# HMC5883_module.net
KiCad netlist of a schematic drawn in Altium Designer
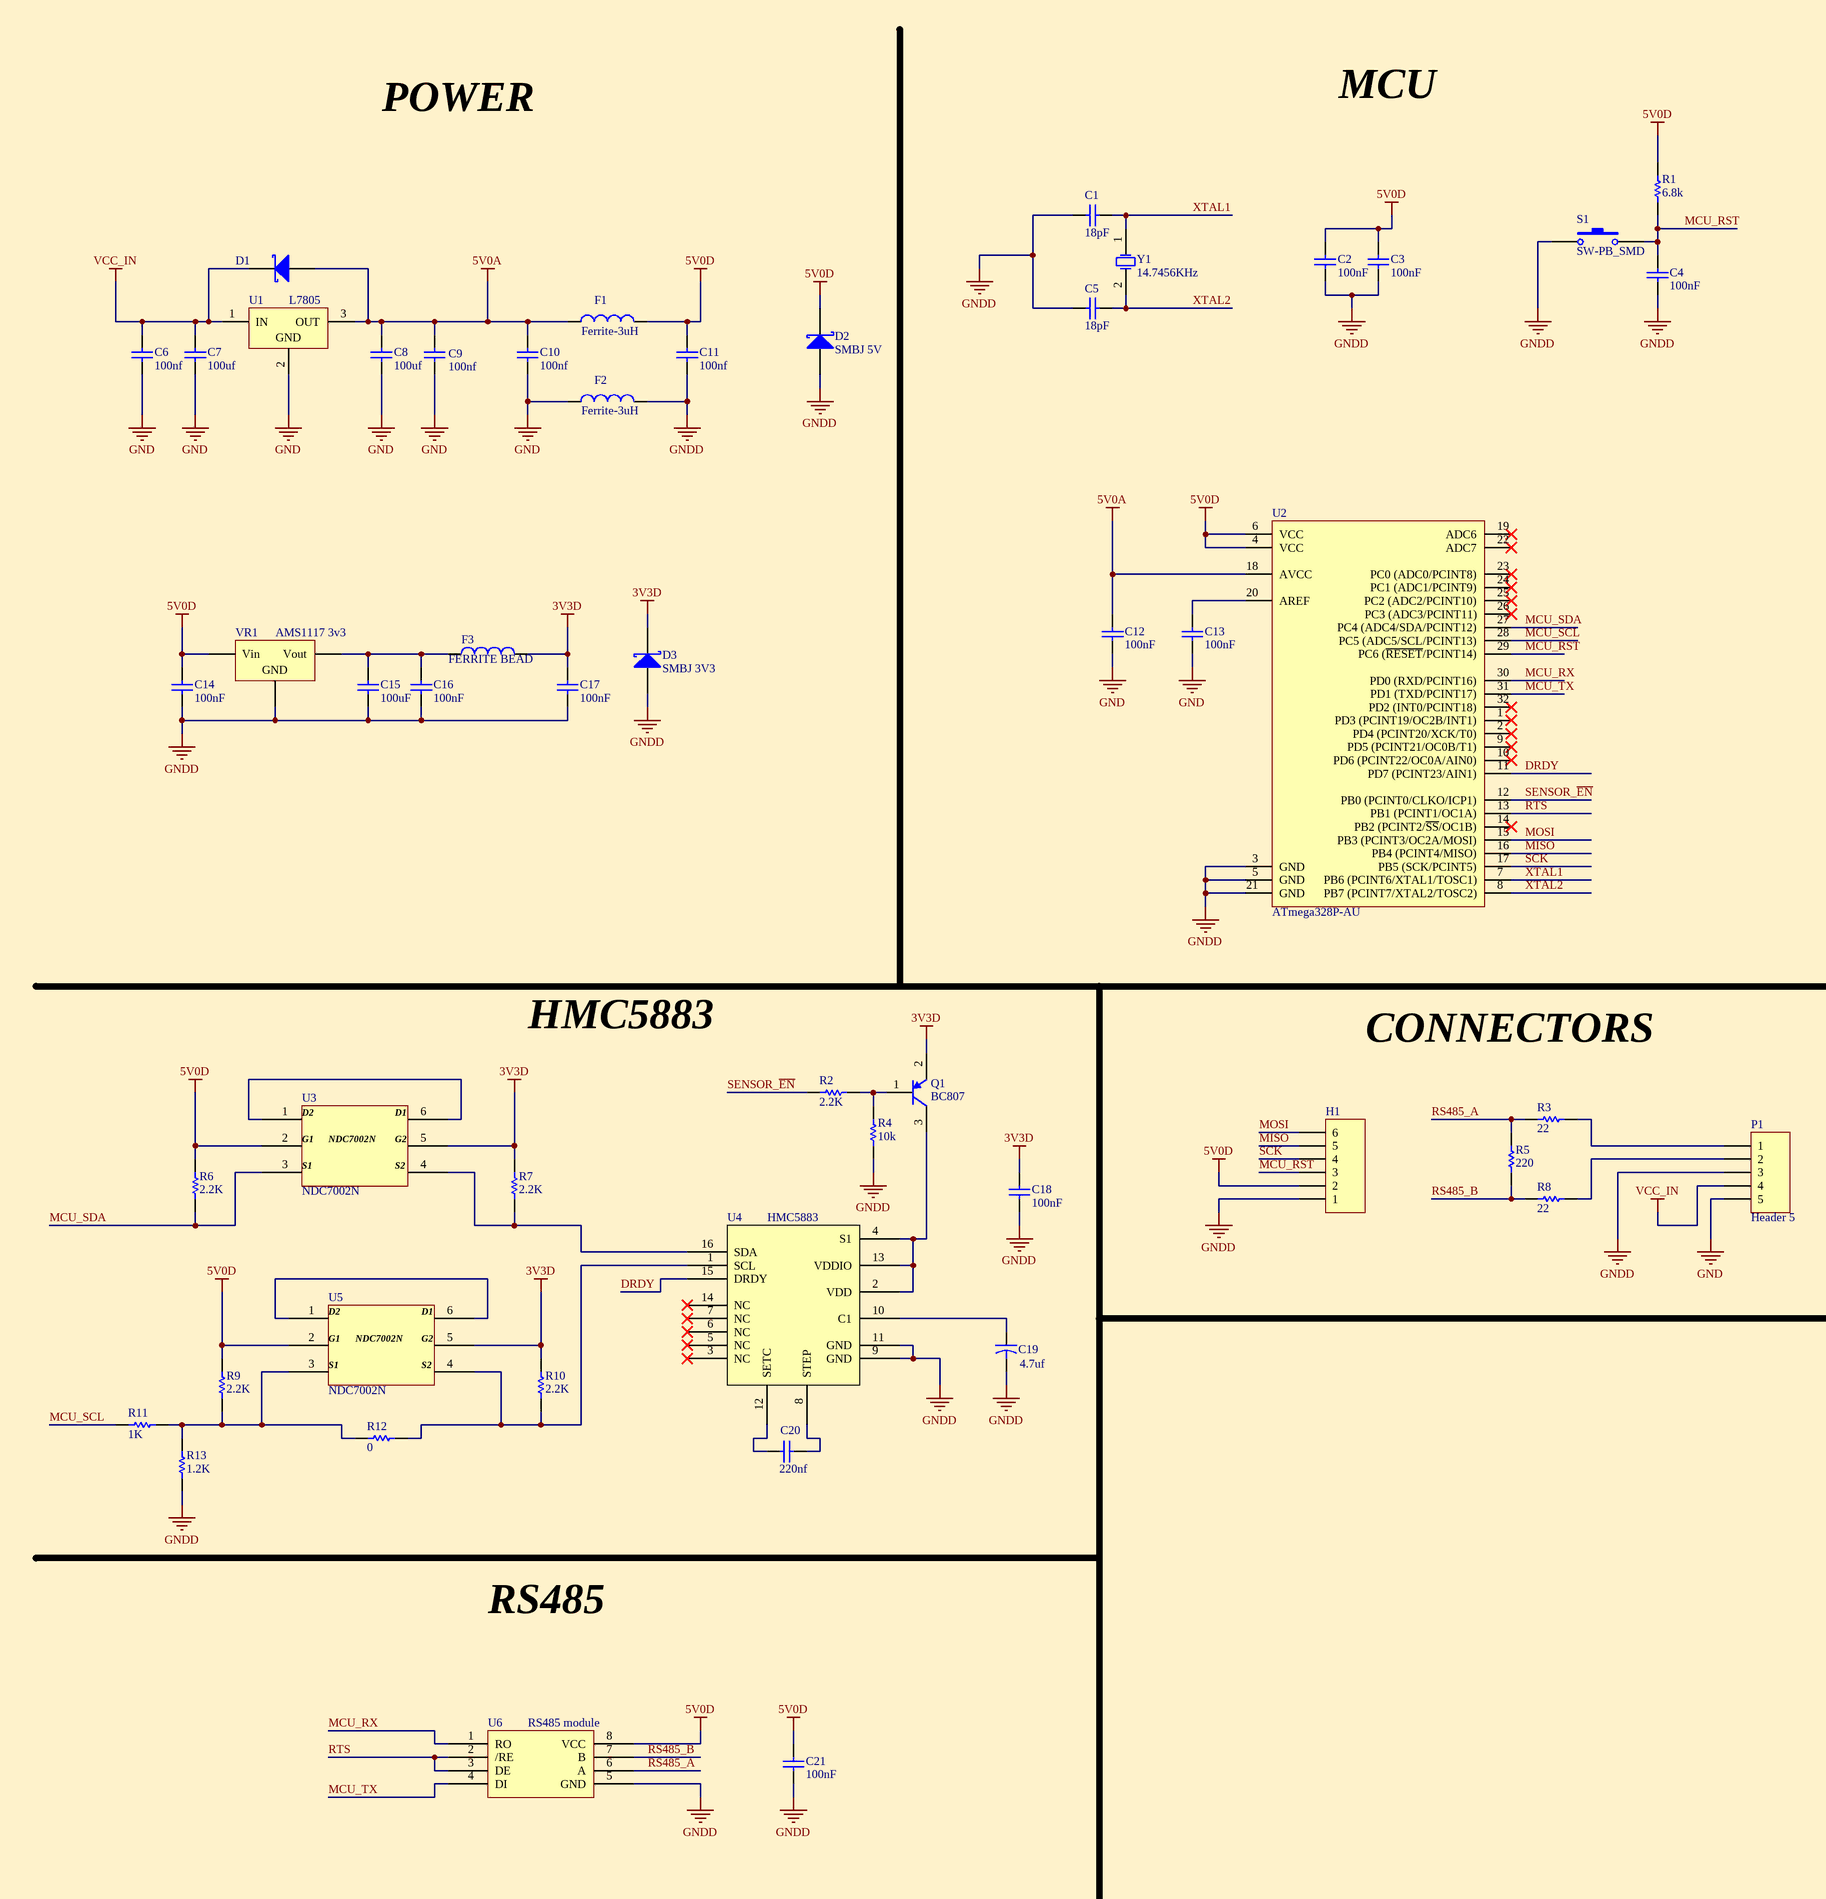
[diagram p0: HMC5883_module.SchDoc, left]
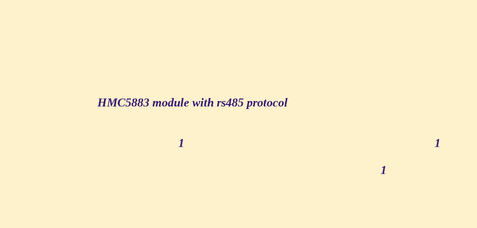
[diagram p1: HMC5883_module.SchDoc, right]

(export (version "E")
  (design (tool "Eeschema 10.0.6"))
  (components
    (comp (ref "C1")
      (value "18pF")
      (footprint "1206")
      (description "Capacitor")
      (fields (field (name "PUBLISHER") "Altium Limited"))
      (libsource (lib "Miscellaneous Devices") (part "Cap"))
    )
    (comp (ref "C2")
      (value "100nF")
      (footprint "1206")
      (description "Capacitor")
      (fields (field (name "PUBLISHER") "Altium Limited"))
      (libsource (lib "Miscellaneous Devices") (part "Cap"))
    )
    (comp (ref "C3")
      (value "100nF")
      (footprint "1206")
      (description "Capacitor")
      (fields (field (name "PUBLISHER") "Altium Limited"))
      (libsource (lib "Miscellaneous Devices") (part "Cap"))
    )
    (comp (ref "C4")
      (value "100nF")
      (footprint "1206")
      (description "Capacitor")
      (fields (field (name "PUBLISHER") "Altium Limited"))
      (libsource (lib "Miscellaneous Devices") (part "Cap"))
    )
    (comp (ref "C5")
      (value "18pF")
      (footprint "1206")
      (description "Capacitor")
      (fields (field (name "PUBLISHER") "Altium Limited"))
      (libsource (lib "Miscellaneous Devices") (part "Cap"))
    )
    (comp (ref "C6")
      (value "100nf")
      (footprint "1206")
      (description "Capacitor, 1206")
      (fields (field (name "PUBLISHER") "Altium Limited"))
      (libsource (lib "Miscellaneous Devices") (part "Cap"))
    )
    (comp (ref "C7")
      (value "100uf")
      (footprint "1206")
      (description "Capacitor, 1206")
      (fields (field (name "PUBLISHER") "Altium Limited"))
      (libsource (lib "Miscellaneous Devices") (part "Cap"))
    )
    (comp (ref "C8")
      (value "100uf")
      (footprint "1206")
      (description "Capacitor, 1206")
      (fields (field (name "PUBLISHER") "Altium Limited"))
      (libsource (lib "Miscellaneous Devices") (part "Cap"))
    )
    (comp (ref "C9")
      (value "100nf")
      (footprint "1206")
      (description "Capacitor, 1206")
      (fields (field (name "PUBLISHER") "Altium Limited"))
      (libsource (lib "Miscellaneous Devices") (part "Cap"))
    )
    (comp (ref "C10")
      (value "100nf")
      (footprint "1206")
      (description "Capacitor, 1206")
      (fields (field (name "PUBLISHER") "Altium Limited"))
      (libsource (lib "Miscellaneous Devices") (part "Cap"))
    )
    (comp (ref "C11")
      (value "100nf")
      (footprint "1206")
      (description "Capacitor, 1206")
      (fields (field (name "PUBLISHER") "Altium Limited"))
      (libsource (lib "Miscellaneous Devices") (part "Cap"))
    )
    (comp (ref "C12")
      (value "100nF")
      (footprint "1206")
      (description "Capacitor")
      (fields (field (name "PUBLISHER") "Altium Limited"))
      (libsource (lib "Miscellaneous Devices") (part "Cap"))
    )
    (comp (ref "C13")
      (value "100nF")
      (footprint "1206")
      (description "Capacitor")
      (fields (field (name "PUBLISHER") "Altium Limited"))
      (libsource (lib "Miscellaneous Devices") (part "Cap"))
    )
    (comp (ref "C14")
      (value "100nF")
      (footprint "1206")
      (description "Capacitor")
      (fields (field (name "Comment") "Cap") (field (name "PUBLISHER") "Altium Limited"))
      (libsource (lib "Miscellaneous Devices") (part "Cap"))
    )
    (comp (ref "C15")
      (value "100uF")
      (footprint "1206")
      (description "Capacitor")
      (fields (field (name "Comment") "Cap") (field (name "PUBLISHER") "Altium Limited"))
      (libsource (lib "Miscellaneous Devices") (part "Cap"))
    )
    (comp (ref "C16")
      (value "100nF")
      (footprint "1206")
      (description "Capacitor")
      (fields (field (name "Comment") "Cap") (field (name "PUBLISHER") "Altium Limited"))
      (libsource (lib "Miscellaneous Devices") (part "Cap"))
    )
    (comp (ref "C17")
      (value "100nF")
      (footprint "1206")
      (description "Capacitor")
      (fields (field (name "Comment") "Cap") (field (name "PUBLISHER") "Altium Limited"))
      (libsource (lib "Miscellaneous Devices") (part "Cap"))
    )
    (comp (ref "C18")
      (value "100nF")
      (footprint "1206")
      (description "Capacitor")
      (fields (field (name "Comment") "Cap") (field (name "PUBLISHER") "Altium Limited"))
      (libsource (lib "Miscellaneous Devices") (part "Cap"))
    )
    (comp (ref "C19")
      (value "4.7uf")
      (footprint "CAP_SMD_A")
      (description "TAN")
      (fields (field (name "Comment") "Cap2") (field (name "PUBLISHER") "Altium Limited"))
      (libsource (lib "Miscellaneous Devices") (part "Cap2"))
    )
    (comp (ref "C20")
      (value "220nf")
      (footprint "1206")
      (description "Capacitor")
      (fields (field (name "Comment") "Cap") (field (name "PUBLISHER") "Altium Limited"))
      (libsource (lib "Miscellaneous Devices") (part "Cap"))
    )
    (comp (ref "C21")
      (value "100nF")
      (footprint "1206")
      (description "Capacitor")
      (fields (field (name "Comment") "Cap") (field (name "PUBLISHER") "Altium Limited"))
      (libsource (lib "Miscellaneous Devices") (part "Cap"))
    )
    (comp (ref "D1")
      (value "D Schottky")
      (footprint "ZINER")
      (description "Schottky Diode, 1N4148")
      (fields (field (name "PUBLISHER") "Altium Limited"))
      (libsource (lib "Miscellaneous Devices") (part "D Schottky"))
    )
    (comp (ref "D2")
      (value "SMBJ 5V")
      (footprint "TVS")
      (description "Schottky Rectifier")
      (fields (field (name "PUBLISHER") "Altium Limited"))
      (libsource (lib "Miscellaneous Devices") (part "Diode 18TQ045"))
    )
    (comp (ref "D3")
      (value "SMBJ 3V3")
      (footprint "TVS")
      (description "TVS")
      (fields (field (name "PUBLISHER") "Altium Limited"))
      (libsource (lib "Miscellaneous Devices") (part "Diode 18TQ045"))
    )
    (comp (ref "F1")
      (value "Ferrite-3uH")
      (footprint "1206")
      (description "Inductor")
      (fields (field (name "PUBLISHER") "Altium Limited"))
      (libsource (lib "Miscellaneous Devices") (part "Inductor"))
    )
    (comp (ref "F2")
      (value "Ferrite-3uH")
      (footprint "1206")
      (description "Inductor")
      (fields (field (name "PUBLISHER") "Altium Limited"))
      (libsource (lib "Miscellaneous Devices") (part "Inductor"))
    )
    (comp (ref "F3")
      (value "FERRITE BEAD")
      (footprint "1206")
      (fields (field (name "PUBLISHER") "Altium Limited"))
      (libsource (lib "Miscellaneous Devices") (part "Inductor"))
    )
    (comp (ref "H1")
      (value "White SMD Connector 6pin")
      (footprint "White SMD Connector 6pin B")
      (fields (field (name "PUBLISHER") "Altium Limited"))
      (libsource (lib "Miscellaneous Connectors") (part "Header 6"))
    )
    (comp (ref "P1")
      (value "Header 5")
      (footprint "HDR1X5")
      (description "Header, 5-Pin")
      (fields (field (name "PUBLISHER") "Altium Limited"))
      (libsource (lib "Miscellaneous Connectors") (part "Header 5"))
    )
    (comp (ref "Q1")
      (value "BC807")
      (footprint "SOT-23")
      (description "PNP General Purpose Amplifier")
      (fields (field (name "PUBLISHER") "Altium Limited"))
      (libsource (lib "Miscellaneous Devices") (part "2N3906"))
    )
    (comp (ref "R1")
      (value "6.8k")
      (footprint "1206")
      (description "Resistor, 6.8k")
      (fields (field (name "PUBLISHER") "Altium Limited"))
      (libsource (lib "Miscellaneous Devices") (part "Res1"))
    )
    (comp (ref "R2")
      (value "2.2K")
      (footprint "1206")
      (description "Resistor")
      (fields (field (name "PUBLISHER") "Altium Limited"))
      (libsource (lib "Miscellaneous Devices") (part "Res1"))
    )
    (comp (ref "R3")
      (value "22")
      (footprint "1206")
      (description "Resistor")
      (fields (field (name "PUBLISHER") "Altium Limited"))
      (libsource (lib "Miscellaneous Devices") (part "Res1"))
    )
    (comp (ref "R4")
      (value "10k")
      (footprint "1206")
      (description "Resistor")
      (fields (field (name "PUBLISHER") "Altium Limited"))
      (libsource (lib "Miscellaneous Devices") (part "Res1"))
    )
    (comp (ref "R5")
      (value "220")
      (footprint "1206")
      (description "Resistor")
      (fields (field (name "PUBLISHER") "Altium Limited"))
      (libsource (lib "Miscellaneous Devices") (part "Res1"))
    )
    (comp (ref "R6")
      (value "2.2K")
      (footprint "1206")
      (description "Resistor")
      (fields (field (name "PUBLISHER") "Altium Limited"))
      (libsource (lib "Miscellaneous Devices") (part "Res1"))
    )
    (comp (ref "R7")
      (value "2.2K")
      (footprint "1206")
      (description "Resistor")
      (fields (field (name "PUBLISHER") "Altium Limited"))
      (libsource (lib "Miscellaneous Devices") (part "Res1"))
    )
    (comp (ref "R8")
      (value "22")
      (footprint "1206")
      (description "Resistor")
      (fields (field (name "PUBLISHER") "Altium Limited"))
      (libsource (lib "Miscellaneous Devices") (part "Res1"))
    )
    (comp (ref "R9")
      (value "2.2K")
      (footprint "1206")
      (description "Resistor")
      (fields (field (name "PUBLISHER") "Altium Limited"))
      (libsource (lib "Miscellaneous Devices") (part "Res1"))
    )
    (comp (ref "R10")
      (value "2.2K")
      (footprint "1206")
      (description "Resistor")
      (fields (field (name "PUBLISHER") "Altium Limited"))
      (libsource (lib "Miscellaneous Devices") (part "Res1"))
    )
    (comp (ref "R11")
      (value "1K")
      (footprint "1206")
      (description "Resistor")
      (fields (field (name "PUBLISHER") "Altium Limited"))
      (libsource (lib "Miscellaneous Devices") (part "Res1"))
    )
    (comp (ref "R12")
      (value "0")
      (footprint "1206")
      (description "Resistor")
      (fields (field (name "PUBLISHER") "Altium Limited"))
      (libsource (lib "Miscellaneous Devices") (part "Res1"))
    )
    (comp (ref "R13")
      (value "1.2K")
      (footprint "1206")
      (description "Resistor")
      (fields (field (name "PUBLISHER") "Altium Limited"))
      (libsource (lib "Miscellaneous Devices") (part "Res1"))
    )
    (comp (ref "S1")
      (value "SW-PB_SMD")
      (footprint "PB4x3.2")
      (description "Switch")
      (fields (field (name "PUBLISHER") "Altium Limited"))
      (libsource (lib "Miscellaneous Devices") (part "SW-PB"))
    )
    (comp (ref "U1")
      (value "L7805")
      (footprint "DPAK")
      (description "Positive Voltage Regulator")
      (fields (field (name "PUBLISHER") "Altium Limited"))
      (libsource (lib "ST Power Mgt Voltage Regulator") (part "L7805CD2T"))
    )
    (comp (ref "U2")
      (value "ATmega328P-AU")
      (footprint "32A_L")
      (fields (field (name "PUBLISHER") "Altium Limited"))
      (libsource (lib "Library") (part "ATmega328P-AU"))
    )
    (comp (ref "U3") (value "NDC7002N") (footprint "SOP6") (libsource (lib "NDC7002N") (part "NDC7002N")))
    (comp (ref "U4") (value "HMC5883") (footprint "LCC16") (libsource (lib "Library") (part "HMC5883")))
    (comp (ref "U5") (value "NDC7002N") (footprint "SOP6") (libsource (lib "NDC7002N") (part "NDC7002N")))
    (comp (ref "U6")
      (value "RS485 module")
      (footprint "SOP8")
      (libsource (lib "Schlib_RS485") (part "rs485"))
    )
    (comp (ref "VR1")
      (value "AMS1117 3v3")
      (footprint "LD1117")
      (description "Voltage Regulator")
      (fields (field (name "PUBLISHER") "Altium Limited"))
      (libsource (lib "Miscellaneous Devices") (part "Volt Reg"))
    )
    (comp (ref "Y1")
      (value "14.7456KHz")
      (footprint "XTAL_SMD")
      (description "Crystal Oscillator, 14.7456KHz")
      (fields (field (name "PUBLISHER") "Altium Limited"))
      (libsource (lib "Miscellaneous Devices") (part "XTAL"))
    )
  )
  (nets
    (net (code "1") (name "/DRDY") (class "Default")
      (node (ref "U2") (pin "11") (pinfunction "PD7_(PCINT23/AIN1)_11") (pintype "passive"))
      (node (ref "U4") (pin "15") (pinfunction "DRDY_15") (pintype "passive"))
    )
    (net (code "2") (name "/MCU_RST") (class "Default")
      (node (ref "C4") (pin "2") (pinfunction "2_2") (pintype "passive"))
      (node (ref "H1") (pin "3") (pinfunction "3_3") (pintype "passive"))
      (node (ref "R1") (pin "2") (pinfunction "2_2") (pintype "passive"))
      (node (ref "S1") (pin "2") (pinfunction "2_2") (pintype "passive"))
      (node (ref "U2") (pin "29") (pinfunction "PC6_(~{RESET}/PCINT14)_29") (pintype "passive"))
    )
    (net (code "3") (name "/MCU_RX") (class "Default")
      (node (ref "U2") (pin "30") (pinfunction "PD0_(RXD/PCINT16)_30") (pintype "passive"))
      (node (ref "U6") (pin "1") (pinfunction "RO_1") (pintype "passive"))
    )
    (net (code "4") (name "/MCU_SCL") (class "Default")
      (node (ref "R11") (pin "1") (pinfunction "1_1") (pintype "passive"))
      (node (ref "U2") (pin "28") (pinfunction "PC5_(ADC5/SCL/PCINT13)_28") (pintype "passive"))
    )
    (net (code "5") (name "/MCU_SDA") (class "Default")
      (node (ref "R6") (pin "1") (pinfunction "1_1") (pintype "passive"))
      (node (ref "U2") (pin "27") (pinfunction "PC4_(ADC4/SDA/PCINT12)_27") (pintype "passive"))
      (node (ref "U3") (pin "3") (pintype "passive"))
    )
    (net (code "6") (name "/MCU_TX") (class "Default")
      (node (ref "U2") (pin "31") (pinfunction "PD1_(TXD/PCINT17)_31") (pintype "passive"))
      (node (ref "U6") (pin "4") (pinfunction "DI_4") (pintype "passive"))
    )
    (net (code "7") (name "/MISO") (class "Default")
      (node (ref "H1") (pin "5") (pinfunction "5_5") (pintype "passive"))
      (node (ref "U2") (pin "16") (pinfunction "PB4_(PCINT4/MISO)_16") (pintype "passive"))
    )
    (net (code "8") (name "/MOSI") (class "Default")
      (node (ref "H1") (pin "6") (pinfunction "6_6") (pintype "passive"))
      (node (ref "U2") (pin "15") (pinfunction "PB3_(PCINT3/OC2A/MOSI)_15") (pintype "passive"))
    )
    (net (code "9") (name "/RS485_A") (class "Default")
      (node (ref "R3") (pin "1") (pinfunction "1_1") (pintype "passive"))
      (node (ref "R5") (pin "1") (pinfunction "1_1") (pintype "passive"))
      (node (ref "U6") (pin "6") (pinfunction "A_6") (pintype "passive"))
    )
    (net (code "10") (name "/RS485_B") (class "Default")
      (node (ref "R5") (pin "2") (pinfunction "2_2") (pintype "passive"))
      (node (ref "R8") (pin "1") (pinfunction "1_1") (pintype "passive"))
      (node (ref "U6") (pin "7") (pinfunction "B_7") (pintype "passive"))
    )
    (net (code "11") (name "/RTS") (class "Default")
      (node (ref "U2") (pin "13") (pinfunction "PB1_(PCINT1/OC1A)_13") (pintype "passive"))
      (node (ref "U6") (pin "2") (pinfunction "/RE_2") (pintype "passive"))
      (node (ref "U6") (pin "3") (pinfunction "DE_3") (pintype "passive"))
    )
    (net (code "12") (name "/SCK") (class "Default")
      (node (ref "H1") (pin "4") (pinfunction "4_4") (pintype "passive"))
      (node (ref "U2") (pin "17") (pinfunction "PB5_(SCK/PCINT5)_17") (pintype "passive"))
    )
    (net (code "13") (name "/SENSOR_~{EN}") (class "Default")
      (node (ref "R2") (pin "2") (pinfunction "2_2") (pintype "passive"))
      (node (ref "U2") (pin "12") (pinfunction "PB0_(PCINT0/CLKO/ICP1)_12") (pintype "passive"))
    )
    (net (code "14") (name "/XTAL1") (class "Default")
      (node (ref "C1") (pin "2") (pinfunction "2_2") (pintype "passive"))
      (node (ref "U2") (pin "7") (pinfunction "PB6_(PCINT6/XTAL1/TOSC1)_7") (pintype "passive"))
      (node (ref "Y1") (pin "1") (pinfunction "OSC1_1") (pintype "passive"))
    )
    (net (code "15") (name "/XTAL2") (class "Default")
      (node (ref "C5") (pin "2") (pinfunction "2_2") (pintype "passive"))
      (node (ref "U2") (pin "8") (pinfunction "PB7_(PCINT7/XTAL2/TOSC2)_8") (pintype "passive"))
      (node (ref "Y1") (pin "2") (pinfunction "OSC2_2") (pintype "passive"))
    )
    (net (code "16") (name "3V3D") (class "Default")
      (node (ref "C17") (pin "2") (pinfunction "2_2") (pintype "passive"))
      (node (ref "C18") (pin "2") (pinfunction "2_2") (pintype "passive"))
      (node (ref "D3") (pin "1") (pinfunction "K_1") (pintype "passive"))
      (node (ref "F3") (pin "2") (pinfunction "2_2") (pintype "passive"))
      (node (ref "Q1") (pin "2") (pinfunction "E_2") (pintype "passive"))
      (node (ref "R10") (pin "2") (pinfunction "2_2") (pintype "passive"))
      (node (ref "R7") (pin "2") (pinfunction "2_2") (pintype "passive"))
      (node (ref "U3") (pin "5") (pinfunction "5_5") (pintype "passive"))
      (node (ref "U5") (pin "5") (pinfunction "5_5") (pintype "passive"))
    )
    (net (code "17") (name "5V0A") (class "Default")
      (node (ref "C10") (pin "2") (pinfunction "2_2") (pintype "passive"))
      (node (ref "C12") (pin "2") (pinfunction "2_2") (pintype "passive"))
      (node (ref "C8") (pin "2") (pinfunction "2_2") (pintype "passive"))
      (node (ref "C9") (pin "2") (pinfunction "2_2") (pintype "passive"))
      (node (ref "D1") (pin "1") (pinfunction "A_1") (pintype "passive"))
      (node (ref "F1") (pin "1") (pinfunction "1_1") (pintype "passive"))
      (node (ref "U1") (pin "3") (pinfunction "OUT_3") (pintype "power_in"))
      (node (ref "U2") (pin "18") (pinfunction "AVCC_18") (pintype "passive"))
    )
    (net (code "18") (name "5V0D") (class "Default")
      (node (ref "C11") (pin "2") (pinfunction "2_2") (pintype "passive"))
      (node (ref "C14") (pin "2") (pinfunction "2_2") (pintype "passive"))
      (node (ref "C2") (pin "2") (pinfunction "2_2") (pintype "passive"))
      (node (ref "C21") (pin "2") (pinfunction "2_2") (pintype "passive"))
      (node (ref "C3") (pin "2") (pinfunction "2_2") (pintype "passive"))
      (node (ref "D2") (pin "1") (pinfunction "K_1") (pintype "passive"))
      (node (ref "F1") (pin "2") (pinfunction "2_2") (pintype "passive"))
      (node (ref "H1") (pin "2") (pinfunction "2_2") (pintype "passive"))
      (node (ref "R1") (pin "1") (pinfunction "1_1") (pintype "passive"))
      (node (ref "R6") (pin "2") (pinfunction "2_2") (pintype "passive"))
      (node (ref "R9") (pin "2") (pinfunction "2_2") (pintype "passive"))
      (node (ref "U2") (pin "4") (pinfunction "VCC_4") (pintype "passive"))
      (node (ref "U2") (pin "6") (pinfunction "VCC_6") (pintype "passive"))
      (node (ref "U3") (pin "2") (pintype "passive"))
      (node (ref "U5") (pin "2") (pintype "passive"))
      (node (ref "U6") (pin "8") (pinfunction "VCC_8") (pintype "passive"))
      (node (ref "VR1") (pin "3") (pinfunction "Vin_3") (pintype "passive"))
    )
    (net (code "19") (name "GND") (class "Default")
      (node (ref "C10") (pin "1") (pinfunction "1_1") (pintype "passive"))
      (node (ref "C12") (pin "1") (pinfunction "1_1") (pintype "passive"))
      (node (ref "C13") (pin "1") (pinfunction "1_1") (pintype "passive"))
      (node (ref "C6") (pin "1") (pinfunction "1_1") (pintype "passive"))
      (node (ref "C7") (pin "1") (pinfunction "1_1") (pintype "passive"))
      (node (ref "C8") (pin "1") (pinfunction "1_1") (pintype "passive"))
      (node (ref "C9") (pin "1") (pinfunction "1_1") (pintype "passive"))
      (node (ref "F2") (pin "1") (pinfunction "1_1") (pintype "passive"))
      (node (ref "P1") (pin "5") (pinfunction "5_5") (pintype "passive"))
      (node (ref "U1") (pin "2") (pinfunction "GND_2") (pintype "power_in"))
    )
    (net (code "20") (name "GNDD") (class "Default")
      (node (ref "C1") (pin "1") (pinfunction "1_1") (pintype "passive"))
      (node (ref "C11") (pin "1") (pinfunction "1_1") (pintype "passive"))
      (node (ref "C14") (pin "1") (pinfunction "1_1") (pintype "passive"))
      (node (ref "C15") (pin "1") (pinfunction "1_1") (pintype "passive"))
      (node (ref "C16") (pin "1") (pinfunction "1_1") (pintype "passive"))
      (node (ref "C17") (pin "1") (pinfunction "1_1") (pintype "passive"))
      (node (ref "C18") (pin "1") (pinfunction "1_1") (pintype "passive"))
      (node (ref "C19") (pin "2") (pinfunction "2_2") (pintype "passive"))
      (node (ref "C2") (pin "1") (pinfunction "1_1") (pintype "passive"))
      (node (ref "C21") (pin "1") (pinfunction "1_1") (pintype "passive"))
      (node (ref "C3") (pin "1") (pinfunction "1_1") (pintype "passive"))
      (node (ref "C4") (pin "1") (pinfunction "1_1") (pintype "passive"))
      (node (ref "C5") (pin "1") (pinfunction "1_1") (pintype "passive"))
      (node (ref "D2") (pin "2") (pinfunction "A_2") (pintype "passive"))
      (node (ref "D3") (pin "2") (pinfunction "A_2") (pintype "passive"))
      (node (ref "F2") (pin "2") (pinfunction "2_2") (pintype "passive"))
      (node (ref "H1") (pin "1") (pinfunction "1_1") (pintype "passive"))
      (node (ref "P1") (pin "3") (pinfunction "3_3") (pintype "passive"))
      (node (ref "R13") (pin "2") (pinfunction "2_2") (pintype "passive"))
      (node (ref "R4") (pin "2") (pinfunction "2_2") (pintype "passive"))
      (node (ref "S1") (pin "1") (pinfunction "1_1") (pintype "passive"))
      (node (ref "U2") (pin "21") (pinfunction "GND_21") (pintype "passive"))
      (node (ref "U2") (pin "3") (pinfunction "GND_3") (pintype "passive"))
      (node (ref "U2") (pin "5") (pinfunction "GND_5") (pintype "passive"))
      (node (ref "U4") (pin "11") (pinfunction "GND_11") (pintype "passive"))
      (node (ref "U4") (pin "9") (pinfunction "GND_9") (pintype "passive"))
      (node (ref "U6") (pin "5") (pinfunction "GND_5") (pintype "passive"))
      (node (ref "VR1") (pin "1") (pinfunction "GND_1") (pintype "passive"))
    )
    (net (code "21") (name "Net-(P1-Pad1)") (class "Default")
      (node (ref "P1") (pin "1") (pinfunction "1_1") (pintype "passive"))
      (node (ref "R3") (pin "2") (pinfunction "2_2") (pintype "passive"))
    )
    (net (code "22") (name "Net-(P1-Pad2)") (class "Default")
      (node (ref "P1") (pin "2") (pinfunction "2_2") (pintype "passive"))
      (node (ref "R8") (pin "2") (pinfunction "2_2") (pintype "passive"))
    )
    (net (code "23") (name "Net-(Q1-B)") (class "Default")
      (node (ref "Q1") (pin "1") (pinfunction "B_1") (pintype "passive"))
      (node (ref "R2") (pin "1") (pinfunction "1_1") (pintype "passive"))
      (node (ref "R4") (pin "1") (pinfunction "1_1") (pintype "passive"))
    )
    (net (code "24") (name "Net-(Q1-C)") (class "Default")
      (node (ref "Q1") (pin "3") (pinfunction "C_3") (pintype "passive"))
      (node (ref "U4") (pin "13") (pinfunction "VDDIO_13") (pintype "passive"))
      (node (ref "U4") (pin "2") (pinfunction "VDD_2") (pintype "passive"))
      (node (ref "U4") (pin "4") (pinfunction "S1_4") (pintype "passive"))
    )
    (net (code "25") (name "Net-(R11-Pad2)") (class "Default")
      (node (ref "R11") (pin "2") (pinfunction "2_2") (pintype "passive"))
      (node (ref "R12") (pin "1") (pinfunction "1_1") (pintype "passive"))
      (node (ref "R13") (pin "1") (pinfunction "1_1") (pintype "passive"))
      (node (ref "R9") (pin "1") (pinfunction "1_1") (pintype "passive"))
      (node (ref "U5") (pin "3") (pintype "passive"))
    )
    (net (code "26") (name "Net-(U2-AREF)") (class "Default")
      (node (ref "C13") (pin "2") (pinfunction "2_2") (pintype "passive"))
      (node (ref "U2") (pin "20") (pinfunction "AREF_20") (pintype "passive"))
    )
    (net (code "27") (name "Net-(U3-Pad1)") (class "Default")
      (node (ref "U3") (pin "1") (pintype "passive"))
      (node (ref "U3") (pin "6") (pinfunction "6_6") (pintype "passive"))
    )
    (net (code "28") (name "Net-(U4-C1)") (class "Default")
      (node (ref "C19") (pin "1") (pinfunction "1_1") (pintype "passive"))
      (node (ref "U4") (pin "10") (pinfunction "C1_10") (pintype "passive"))
    )
    (net (code "29") (name "Net-(U4-SCL)") (class "Default")
      (node (ref "R10") (pin "1") (pinfunction "1_1") (pintype "passive"))
      (node (ref "R12") (pin "2") (pinfunction "2_2") (pintype "passive"))
      (node (ref "U4") (pin "1") (pinfunction "SCL_1") (pintype "passive"))
      (node (ref "U5") (pin "4") (pinfunction "4_4") (pintype "passive"))
    )
    (net (code "30") (name "Net-(U4-SDA)") (class "Default")
      (node (ref "R7") (pin "1") (pinfunction "1_1") (pintype "passive"))
      (node (ref "U3") (pin "4") (pinfunction "4_4") (pintype "passive"))
      (node (ref "U4") (pin "16") (pinfunction "SDA_16") (pintype "passive"))
    )
    (net (code "31") (name "Net-(U4-SETC)") (class "Default")
      (node (ref "C20") (pin "2") (pinfunction "2_2") (pintype "passive"))
      (node (ref "U4") (pin "12") (pinfunction "SETC_12") (pintype "passive"))
    )
    (net (code "32") (name "Net-(U4-STEP)") (class "Default")
      (node (ref "C20") (pin "1") (pinfunction "1_1") (pintype "passive"))
      (node (ref "U4") (pin "8") (pinfunction "STEP_8") (pintype "passive"))
    )
    (net (code "33") (name "Net-(U5-Pad1)") (class "Default")
      (node (ref "U5") (pin "1") (pintype "passive"))
      (node (ref "U5") (pin "6") (pinfunction "6_6") (pintype "passive"))
    )
    (net (code "34") (name "Net-(VR1-Vout)") (class "Default")
      (node (ref "C15") (pin "2") (pinfunction "2_2") (pintype "passive"))
      (node (ref "C16") (pin "2") (pinfunction "2_2") (pintype "passive"))
      (node (ref "F3") (pin "1") (pinfunction "1_1") (pintype "passive"))
      (node (ref "VR1") (pin "2") (pinfunction "Vout_2") (pintype "passive"))
    )
    (net (code "35") (name "VCC_IN") (class "Default")
      (node (ref "C6") (pin "2") (pinfunction "2_2") (pintype "passive"))
      (node (ref "C7") (pin "2") (pinfunction "2_2") (pintype "passive"))
      (node (ref "D1") (pin "2") (pinfunction "K_2") (pintype "passive"))
      (node (ref "P1") (pin "4") (pinfunction "4_4") (pintype "passive"))
      (node (ref "U1") (pin "1") (pinfunction "IN_1") (pintype "power_in"))
    )
    (net (code "36") (name "unconnected-(U2-ADC6-Pad19)") (class "Default")
      (node (ref "U2") (pin "19") (pinfunction "ADC6_19") (pintype "passive+no_connect"))
    )
    (net (code "37") (name "unconnected-(U2-ADC7-Pad22)") (class "Default")
      (node (ref "U2") (pin "22") (pinfunction "ADC7_22") (pintype "passive+no_connect"))
    )
    (net (code "38") (name "unconnected-(U2-PB2_(PCINT2{slash}~{SS}{slash}OC1B)-Pad14)") (class "Default")
      (node (ref "U2") (pin "14") (pinfunction "PB2_(PCINT2/~{SS}/OC1B)_14") (pintype "passive+no_connect"))
    )
    (net (code "39") (name "unconnected-(U2-PC0_(ADC0{slash}PCINT8)-Pad23)") (class "Default")
      (node (ref "U2") (pin "23") (pinfunction "PC0_(ADC0/PCINT8)_23") (pintype "passive+no_connect"))
    )
    (net (code "40") (name "unconnected-(U2-PC1_(ADC1{slash}PCINT9)-Pad24)") (class "Default")
      (node (ref "U2") (pin "24") (pinfunction "PC1_(ADC1/PCINT9)_24") (pintype "passive+no_connect"))
    )
    (net (code "41") (name "unconnected-(U2-PC2_(ADC2{slash}PCINT10)-Pad25)") (class "Default")
      (node (ref "U2") (pin "25") (pinfunction "PC2_(ADC2/PCINT10)_25") (pintype "passive+no_connect"))
    )
    (net (code "42") (name "unconnected-(U2-PC3_(ADC3{slash}PCINT11)-Pad26)") (class "Default")
      (node (ref "U2") (pin "26") (pinfunction "PC3_(ADC3/PCINT11)_26") (pintype "passive+no_connect"))
    )
    (net (code "43") (name "unconnected-(U2-PD2_(INT0{slash}PCINT18)-Pad32)") (class "Default")
      (node (ref "U2") (pin "32") (pinfunction "PD2_(INT0/PCINT18)_32") (pintype "passive+no_connect"))
    )
    (net (code "44") (name "unconnected-(U2-PD3_(PCINT19{slash}OC2B{slash}INT1)-Pad1)") (class "Default")
      (node (ref "U2") (pin "1") (pinfunction "PD3_(PCINT19/OC2B/INT1)_1") (pintype "passive+no_connect"))
    )
    (net (code "45") (name "unconnected-(U2-PD4_(PCINT20{slash}XCK{slash}T0)-Pad2)") (class "Default")
      (node (ref "U2") (pin "2") (pinfunction "PD4_(PCINT20/XCK/T0)_2") (pintype "passive+no_connect"))
    )
    (net (code "46") (name "unconnected-(U2-PD5_(PCINT21{slash}OC0B{slash}T1)-Pad9)") (class "Default")
      (node (ref "U2") (pin "9") (pinfunction "PD5_(PCINT21/OC0B/T1)_9") (pintype "passive+no_connect"))
    )
    (net (code "47") (name "unconnected-(U2-PD6_(PCINT22{slash}OC0A{slash}AIN0)-Pad10)") (class "Default")
      (node (ref "U2") (pin "10") (pinfunction "PD6_(PCINT22/OC0A/AIN0)_10") (pintype "passive+no_connect"))
    )
    (net (code "48") (name "unconnected-(U4-NC-Pad3)") (class "Default")
      (node (ref "U4") (pin "3") (pinfunction "NC_3") (pintype "passive+no_connect"))
    )
    (net (code "49") (name "unconnected-(U4-NC-Pad5)") (class "Default")
      (node (ref "U4") (pin "5") (pinfunction "NC_5") (pintype "passive+no_connect"))
    )
    (net (code "50") (name "unconnected-(U4-NC-Pad6)") (class "Default")
      (node (ref "U4") (pin "6") (pinfunction "NC_6") (pintype "passive+no_connect"))
    )
    (net (code "51") (name "unconnected-(U4-NC-Pad7)") (class "Default")
      (node (ref "U4") (pin "7") (pinfunction "NC_7") (pintype "passive+no_connect"))
    )
    (net (code "52") (name "unconnected-(U4-NC-Pad14)") (class "Default")
      (node (ref "U4") (pin "14") (pinfunction "NC_14") (pintype "passive+no_connect"))
    )
  )
)
